# MCU047F_Main.net
KiCad netlist of a schematic drawn in Altium Designer
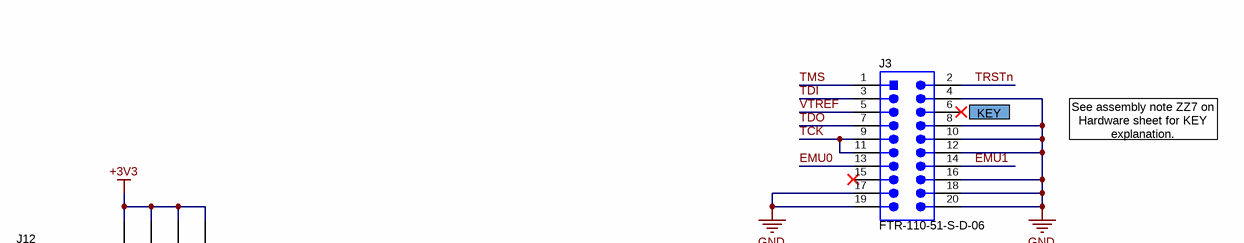
[diagram p0: MCU047F_Main.SchDoc, top left]
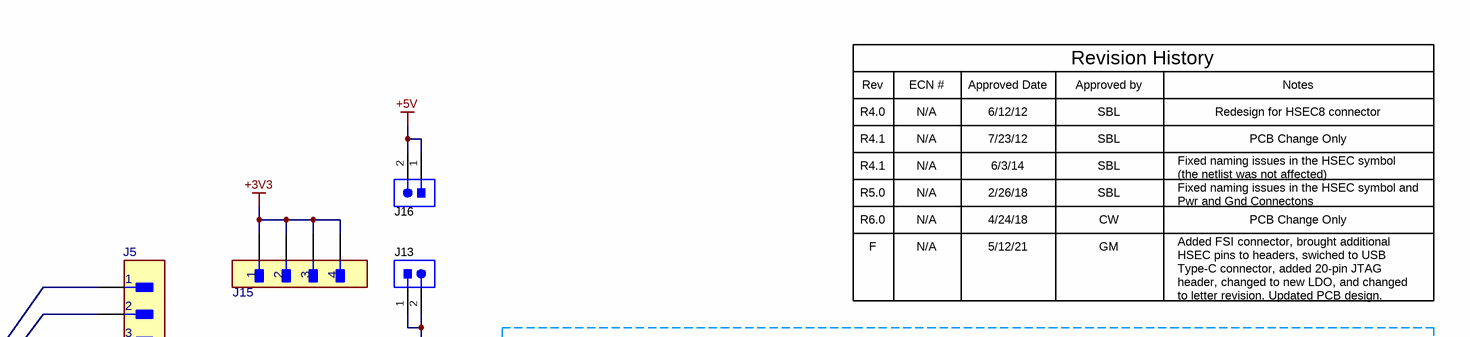
[diagram p1: MCU047F_Main.SchDoc, top right]
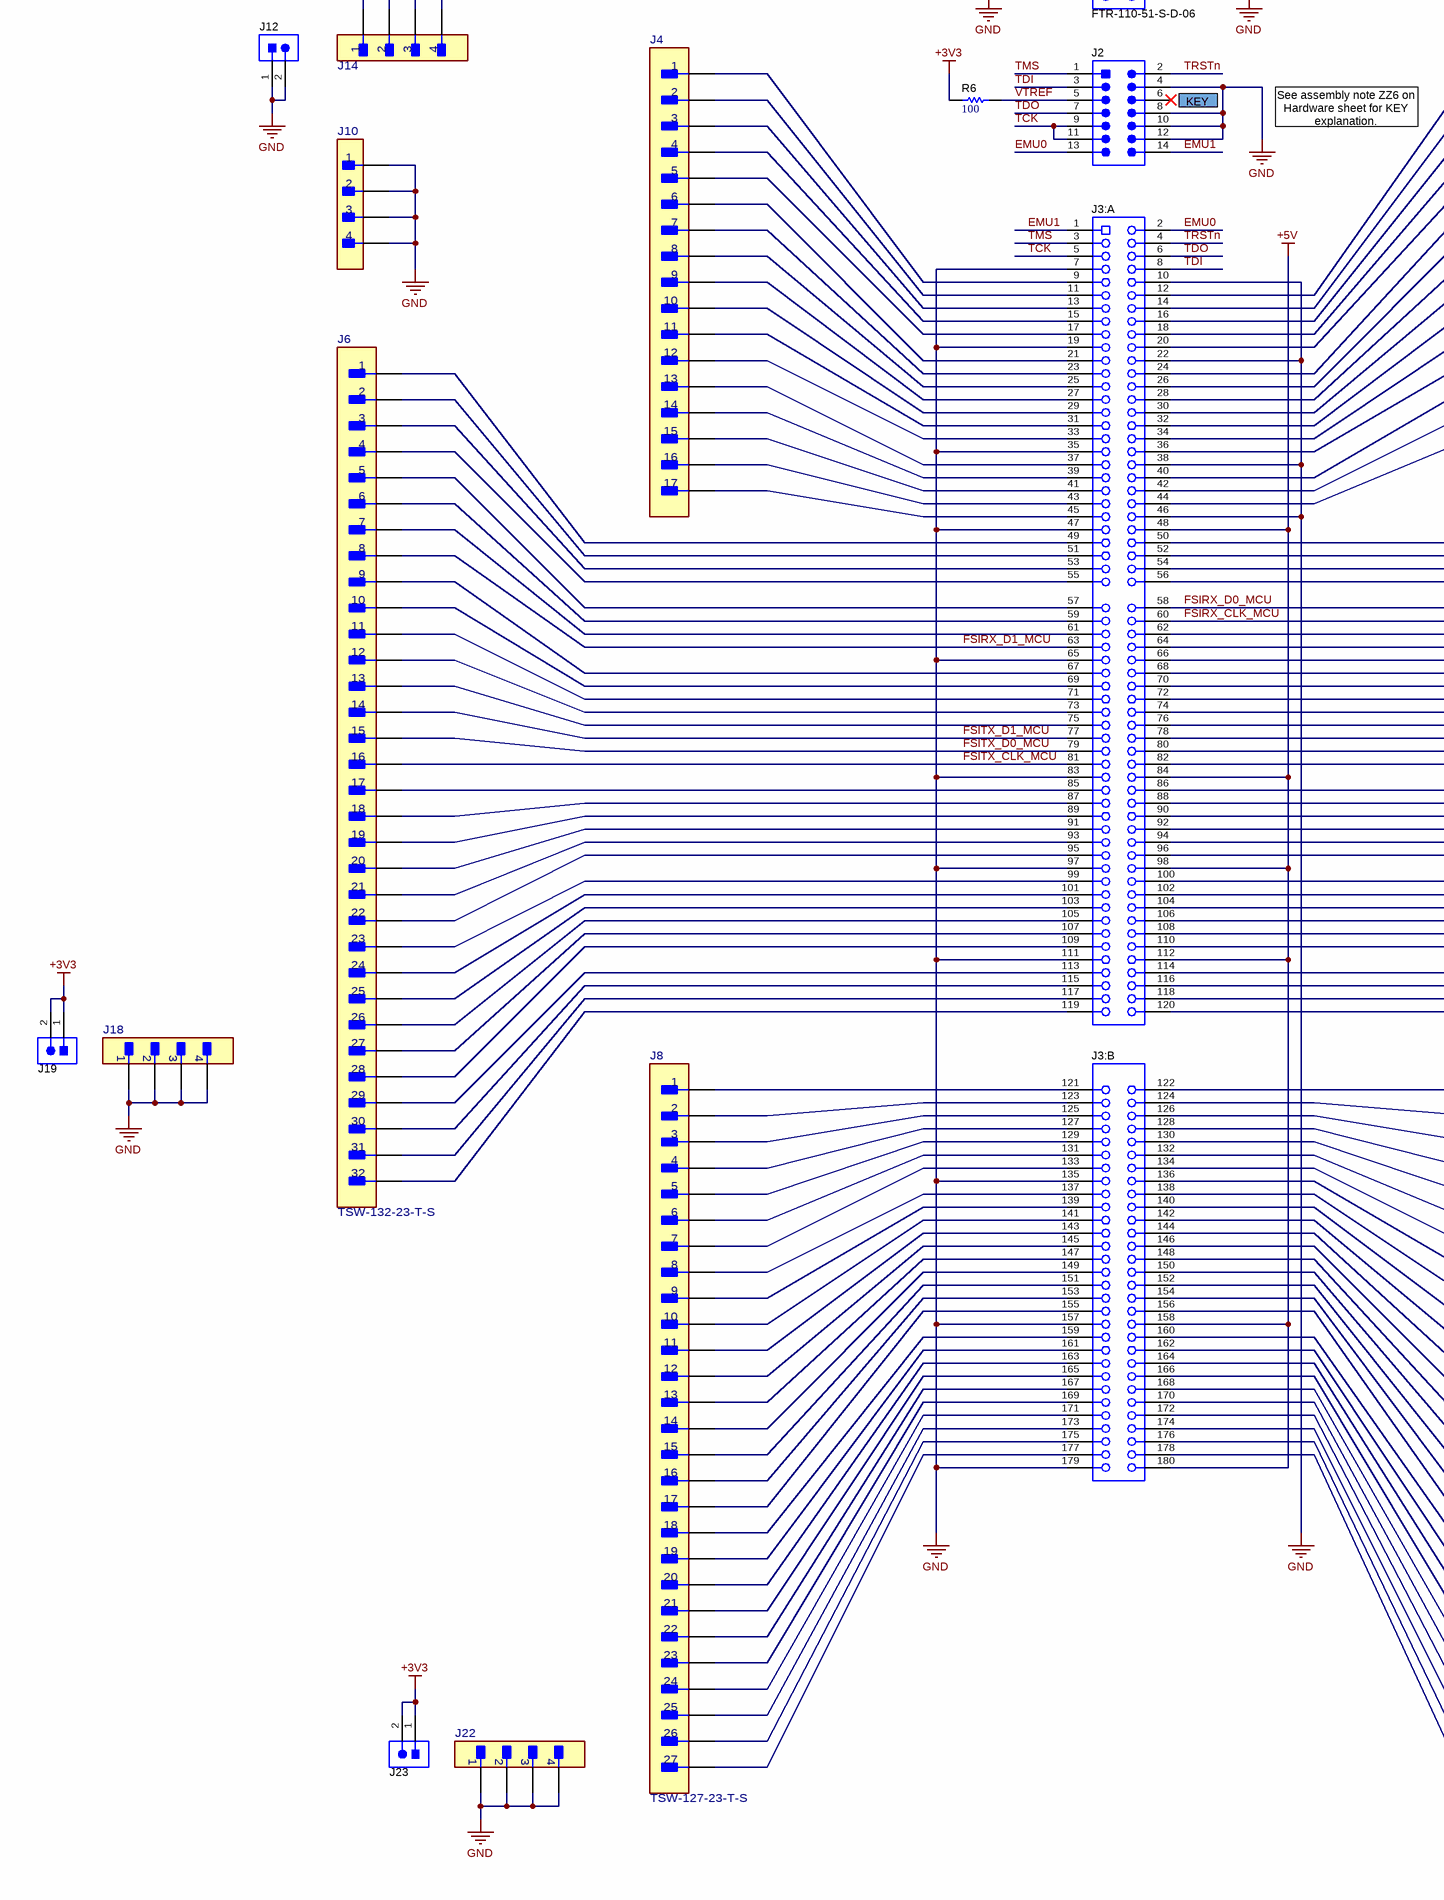
[diagram p2: MCU047F_Main.SchDoc, bottom left]
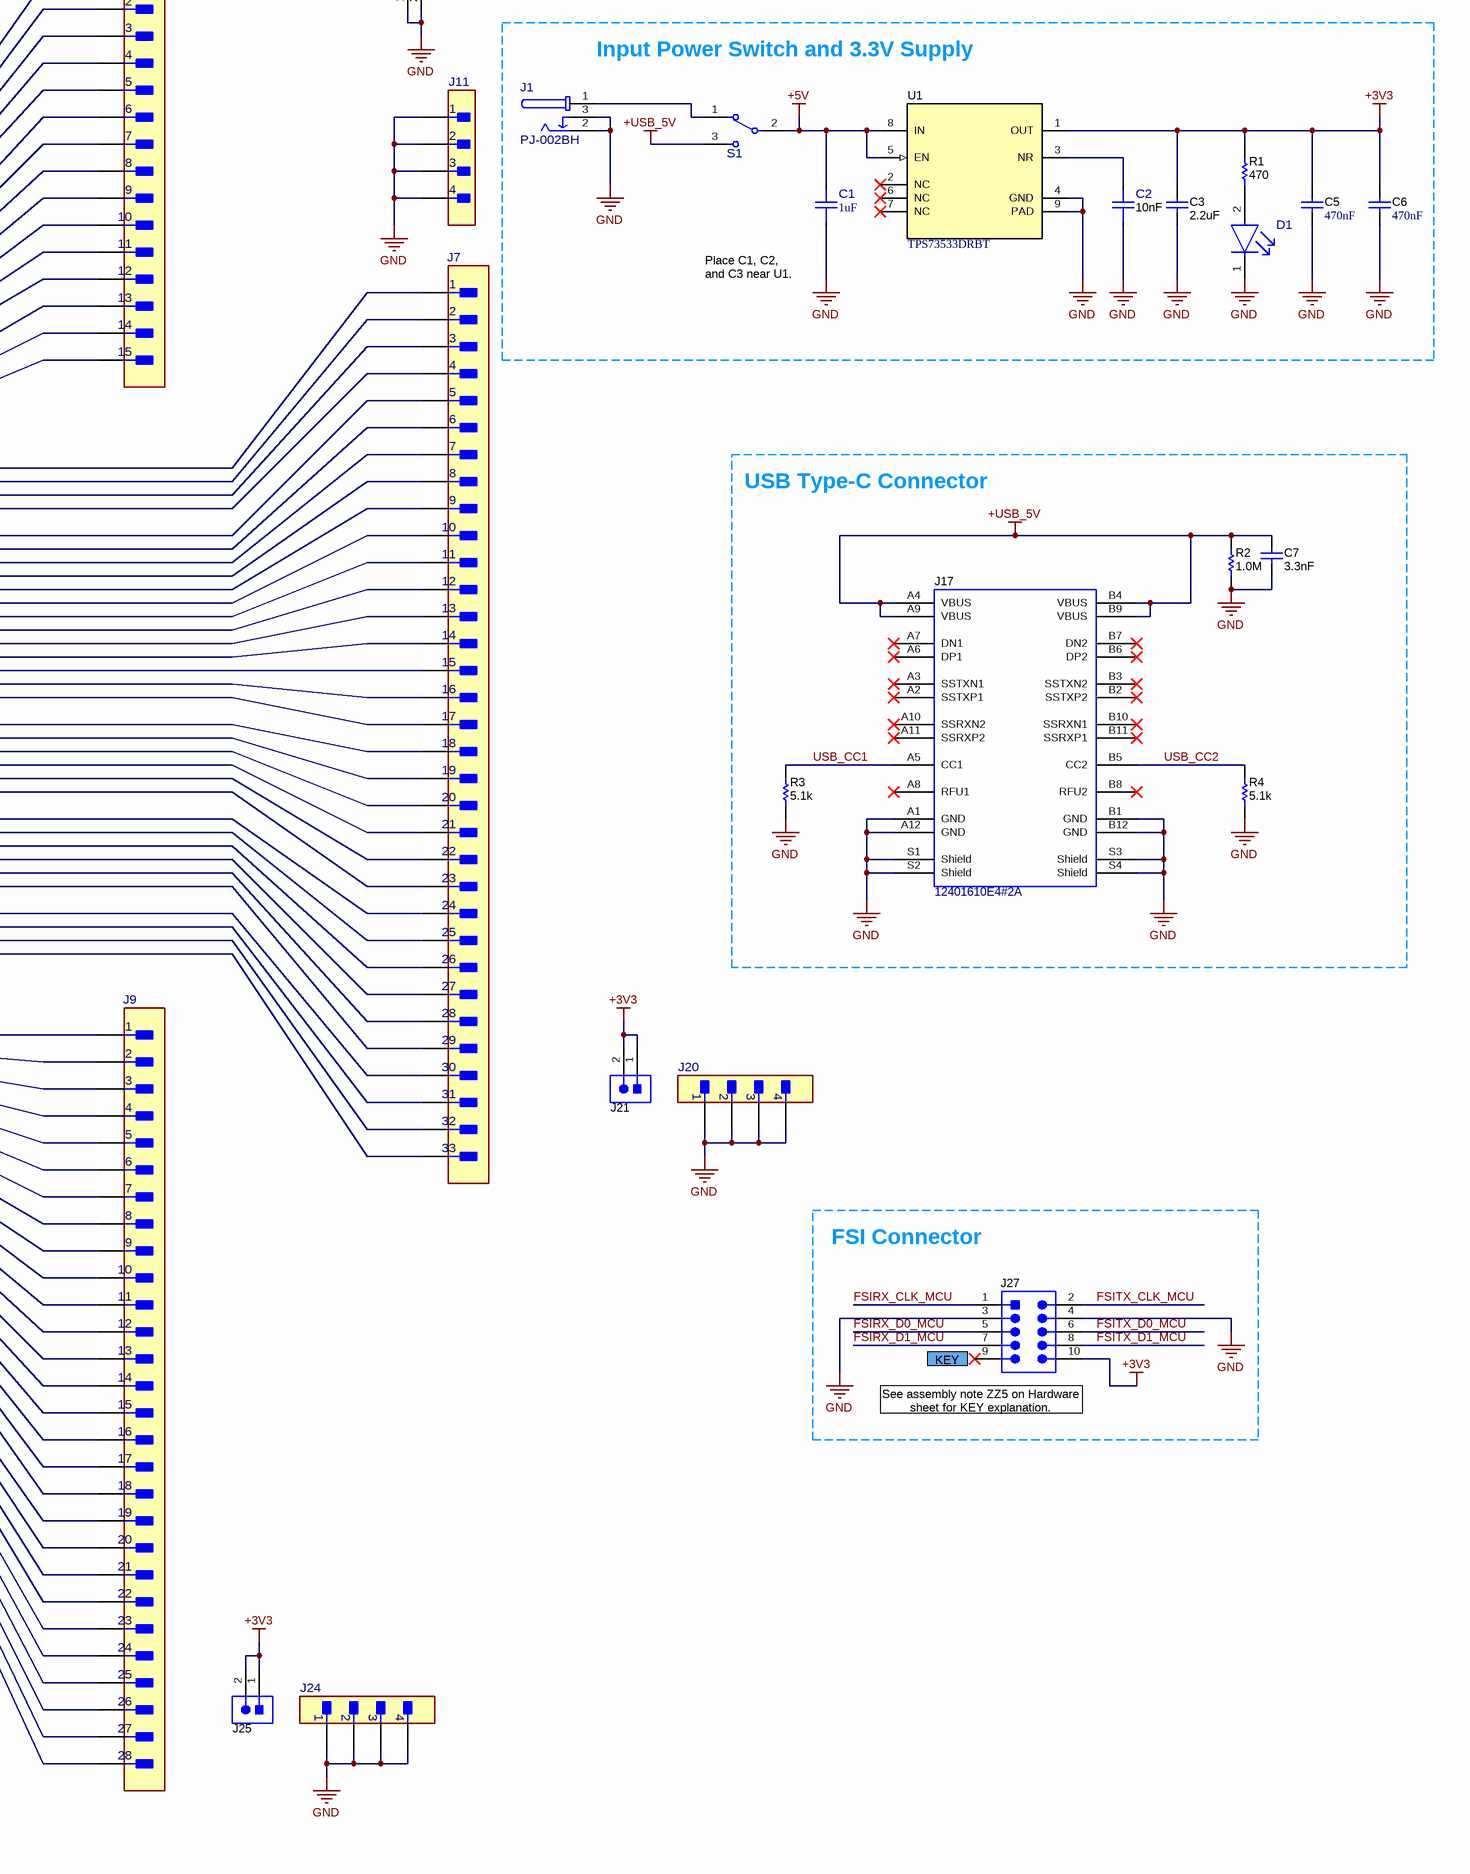
[diagram p3: MCU047F_Main.SchDoc, bottom right]

(export (version "E")
  (design (tool "Eeschema 10.0.6"))
  (components
    (comp (ref "C1")
      (value "C0603C105K8PAC7411")
      (footprint "FP-C0603C105K8PAC7411_0603-MFG")
      (description "1uF ±10% 10V Ceramic Capacitor X5R 0603 (1608 Metric)")
      (fields
        (field (name "MANUFACTURER") "KEMET")
        (field (name "VALUEDISPLAYED") "1uF")
        (field (name "MOUSER PART NUMBER") "80-C0603C105K8PLR")
      )
      (libsource (lib "Altium Vault - TI") (part "SYM-C0603C105K8PAC7411"))
    )
    (comp (ref "C2")
      (value "C0603C103K9RACTU")
      (footprint "FP-C0603C103K9RACTU_0603-MFG")
      (description "10000pF ±10% 6.3V Ceramic Capacitor X7R 0603 (1608 Metric)")
      (fields
        (field (name "DIGIKEY PART NUMBER") "399-8988-1-ND")
        (field (name "MANUFACTURER") "Kemet")
        (field (name "CAP_F") "10nF")
      )
      (libsource (lib "Altium Vault - TI") (part "SYM-C0603C103K9RACTU"))
    )
    (comp (ref "C3")
      (value "JMK107BJ225KAHT")
      (footprint "0603")
      (description "CAP, CERM, 2.2 uF, 6.3 V, +/- 10%, X5R, 0603")
      (fields
        (field (name "MANUFACTURER") "Taiyo Yuden")
        (field (name "VALUEDISPLAYED") "2.2uF")
        (field (name "PUBLISHER") "Texas Instruments")
      )
      (libsource (lib "Altium Vault - TI") (part "Capacitor"))
    )
    (comp (ref "C5")
      (value "0805YC474KAT2A")
      (footprint "0805_HV")
      (description "CAP, CERM, 0.47 uF, 16 V, +/- 10%, X7R, 0805")
      (fields
        (field (name "MANUFACTURER") "AVX")
        (field (name "CAP_F") "470nF")
        (field (name "PUBLISHER") "Texas Instruments")
      )
      (libsource (lib "Altium Vault - TI") (part "Capacitor"))
    )
    (comp (ref "C6")
      (value "0805YC474KAT2A")
      (footprint "0805_HV")
      (description "CAP, CERM, 0.47 uF, 16 V, +/- 10%, X7R, 0805")
      (fields
        (field (name "MANUFACTURER") "AVX")
        (field (name "CAP_F") "470nF")
        (field (name "PUBLISHER") "Texas Instruments")
      )
      (libsource (lib "Altium Vault - TI") (part "Capacitor"))
    )
    (comp (ref "C7")
      (value "C0805C332K5RACTU")
      (footprint "0805_HV")
      (description "CAP, CERM, 3300 pF, 50 V, +/- 10%, X7R, 0805")
      (fields
        (field (name "MANUFACTURER") "Kemet")
        (field (name "CAP_F") "3.3nF")
        (field (name "PUBLISHER") "Texas Instruments")
      )
      (libsource (lib "Altium Vault - TI") (part "Capacitor"))
    )
    (comp (ref "D1")
      (value "PG1112H-TR")
      (footprint "FP-PG1112H-TR_0805-MFG")
      (description "Green 567nm LED Indication - Discrete 2.1V 0805 (2012 Metric)")
      (fields
        (field (name "MOUSER PART NUMBER") "327-PG1112HTR")
        (field (name "MANUFACTURER") "Stanley Electric Co")
      )
      (libsource (lib "Altium Vault - TI") (part "SYM-PG1112H-TR"))
    )
    (comp (ref "J1")
      (value "PJ-002BH")
      (footprint "FP-PJ-002BH_PTH_POWER_CONN_14MM4_9MM0-MFG")
      (fields
        (field (name "MANUFACTURER") "CUI Devices")
        (field (name "DIGIKEY PART NUMBER") "CP-002BH-ND")
        (field (name "MOUSER PART NUMBER") "490-PJ-002BH")
      )
      (libsource (lib "Altium Vault - TI") (part "SYM-PJ-002BH"))
    )
    (comp (ref "J2")
      (value "61301421121")
      (footprint "Wurth_61301421121")
      (description "Header, 2.54mm, 7x2, Gold, TH")
      (fields (field (name "MANUFACTURER") "Wurth Elektronik"))
      (libsource (lib "Altium Vault - TI") (part "Header_7x2"))
    )
    (comp (ref "J3")
      (value "FTR-110-51-S-D-06")
      (footprint "Samtec_FTR-110-51-x-D-06")
      (description "Header, 1.27mm, 10x2, Tin, SMT")
      (fields (field (name "MANUFACTURER") "Samtec"))
      (libsource (lib "Altium Vault - TI") (part "Header_10x2"))
    )
    (comp (ref "J3:A")
      (value "HSEC8-160-01-L-DV-A-BL")
      (footprint "controlCARD-120HSEC")
      (description "C2000 controlCARD-120HSEC connector, SMT")
      (fields (field (name "MANUFACTURER") "Samtec"))
      (libsource (lib "Altium Vault - TI") (part "controlCARD-120HSEC"))
    )
    (comp (ref "J3:B")
      (value "HSEC8-130-01-L-DV-A")
      (footprint "controlCARD-180HSEC-60pinAddon")
      (description "C2000 controlCARD-180HSEC (60-pin addon) connector, SMT")
      (fields (field (name "MANUFACTURER") "Samtec"))
      (libsource (lib "Altium Vault - TI") (part "controlCARD-180HSEC-60pinAddon"))
    )
    (comp (ref "J4")
      (value "TSW-117-23-T-S")
      (footprint "FP-TSW-117-23-T-S_HDR17-MFG")
      (description "Conn Unshrouded Header HDR 17 POS 2.54mm Solder ST Thru-Hole")
      (fields
        (field (name "DIGIKEY PART NUMBER") "SAM1075-17-ND")
        (field (name "MOUSER PART NUMBER") "200-TSW11723TS")
      )
      (libsource (lib "Altium Vault - TI") (part "SYM-TSW-117-23-T-S"))
    )
    (comp (ref "J5")
      (value "TSW-115-23-T-S")
      (footprint "FP-TSW-115-23-T-S_HDR15-MFG")
      (description "Conn Unshrouded Header HDR 15 POS 2.54mm Solder ST Thru-Hole")
      (fields
        (field (name "DIGIKEY PART NUMBER") "SAM1075-15-ND")
        (field (name "MOUSER PART NUMBER") "200-TSW11523TS")
      )
      (libsource (lib "Altium Vault - TI") (part "SYM-TSW-115-23-T-S"))
    )
    (comp (ref "J6")
      (value "TSW-132-23-T-S")
      (footprint "FP-TSW-132-23-T-S_HDR32-MFG")
      (fields
        (field (name "DIGIKEY PART NUMBER") "SAM1075-32-ND")
        (field (name "MOUSER PART NUMBER") "200-TSW13223TS")
        (field (name "MANUFACTURER") "Samtec")
      )
      (libsource (lib "Altium Vault - TI") (part "SYM-TSW-132-23-T-S"))
    )
    (comp (ref "J7")
      (value "TSW-133-23-T-S")
      (footprint "FP-TSW-133-23-T-S_HDR33-MFG")
      (description "Conn Unshrouded Header HDR 33 POS 2.54mm Solder ST Thru-Hole")
      (fields (field (name "OCTOPART PART NUMBER") "26cbefc533f0f90c") (field (name "MANUFACTURER") "Samtec"))
      (libsource (lib "Altium Vault - TI") (part "SYM-TSW-133-23-T-S"))
    )
    (comp (ref "J8")
      (value "TSW-127-23-T-S")
      (footprint "FP-TSW-127-23-T-S_HDR27-MFG")
      (fields (field (name "DIGIKEY PART NUMBER") "SAM1075-27-ND") (field (name "MANUFACTURER") "Samtec"))
      (libsource (lib "Altium Vault - TI") (part "SYM-TSW-127-23-T-S"))
    )
    (comp (ref "J9")
      (value "TSW-128-23-T-S")
      (footprint "FP-TSW-128-23-T-S_HDR28-0")
      (description "Conn Unshrouded Header HDR 28 POS 2.54mm Solder ST Thru-Hole")
      (fields (field (name "DIGIKEY PART NUMBER") "SAM1075-28-ND") (field (name "MANUFACTURER") "Samtec"))
      (libsource (lib "Altium Vault - TI") (part "SYM-TSW-128-23-T-S"))
    )
    (comp (ref "J10")
      (value "TSW-104-23-T-S")
      (footprint "FP-TSW-104-23-T-S_HDR4-MFG")
      (description "Conn Unshrouded Header HDR 4 POS 2.54mm Solder ST Thru-Hole")
      (fields (field (name "MANUFACTURER") "Samtec") (field (name "MOUSER PART NUMBER") "200-TSW10423TS"))
      (libsource (lib "") (part "SYM-TSW-104-23-T-S_1"))
    )
    (comp (ref "J11")
      (value "TSW-104-23-T-S")
      (footprint "FP-TSW-104-23-T-S_HDR4-MFG")
      (description "Conn Unshrouded Header HDR 4 POS 2.54mm Solder ST Thru-Hole")
      (fields (field (name "MANUFACTURER") "Samtec") (field (name "MOUSER PART NUMBER") "200-TSW10423TS"))
      (libsource (lib "") (part "SYM-TSW-104-23-T-S_2"))
    )
    (comp (ref "J12")
      (value "TSW-102-23-T-S")
      (footprint "Samtec_TSW-102-23-X-S")
      (description "Header, 2.54mm, 2x1, Tin, TH")
      (fields (field (name "MANUFACTURER") "Samtec"))
      (libsource (lib "") (part "Header_2x1_1"))
    )
    (comp (ref "J13")
      (value "TSW-102-23-T-S")
      (footprint "Samtec_TSW-102-23-X-S")
      (description "Header, 2.54mm, 2x1, Tin, TH")
      (fields (field (name "MANUFACTURER") "Samtec"))
      (libsource (lib "") (part "Header_2x1_1"))
    )
    (comp (ref "J14")
      (value "TSW-104-23-T-S")
      (footprint "FP-TSW-104-23-T-S_HDR4-MFG")
      (description "Conn Unshrouded Header HDR 4 POS 2.54mm Solder ST Thru-Hole")
      (fields (field (name "MANUFACTURER") "Samtec") (field (name "MOUSER PART NUMBER") "200-TSW10423TS"))
      (libsource (lib "") (part "SYM-TSW-104-23-T-S_3"))
    )
    (comp (ref "J15")
      (value "TSW-104-23-T-S")
      (footprint "FP-TSW-104-23-T-S_HDR4-MFG")
      (description "Conn Unshrouded Header HDR 4 POS 2.54mm Solder ST Thru-Hole")
      (fields (field (name "MANUFACTURER") "Samtec") (field (name "MOUSER PART NUMBER") "200-TSW10423TS"))
      (libsource (lib "") (part "SYM-TSW-104-23-T-S_3"))
    )
    (comp (ref "J16")
      (value "TSW-102-23-T-S")
      (footprint "Samtec_TSW-102-23-X-S")
      (description "Header, 2.54mm, 2x1, Tin, TH")
      (fields (field (name "MANUFACTURER") "Samtec"))
      (libsource (lib "Altium Vault - TI") (part "Header_2x1"))
    )
    (comp (ref "J17")
      (value "12401610E4#2A")
      (footprint "Amphenol_12401610E4_2A")
      (description "Receptacle, 0.5mm, USB TYPE C, R/A, SMT")
      (fields (field (name "MANUFACTURER") "Amphenol Canada") (field (name "PUBLISHER") "Texas Instruments"))
      (libsource (lib "Altium Vault - TI") (part "USB_TYPC-C_4Shield"))
    )
    (comp (ref "J18")
      (value "TSW-104-23-T-S")
      (footprint "FP-TSW-104-23-T-S_HDR4-MFG")
      (description "Conn Unshrouded Header HDR 4 POS 2.54mm Solder ST Thru-Hole")
      (fields (field (name "MANUFACTURER") "Samtec") (field (name "MOUSER PART NUMBER") "200-TSW10423TS"))
      (libsource (lib "Altium Vault - TI") (part "SYM-TSW-104-23-T-S"))
    )
    (comp (ref "J19")
      (value "TSW-102-23-T-S")
      (footprint "Samtec_TSW-102-23-X-S")
      (description "Header, 2.54mm, 2x1, Tin, TH")
      (fields (field (name "MANUFACTURER") "Samtec"))
      (libsource (lib "Altium Vault - TI") (part "Header_2x1"))
    )
    (comp (ref "J20")
      (value "TSW-104-23-T-S")
      (footprint "FP-TSW-104-23-T-S_HDR4-MFG")
      (description "Conn Unshrouded Header HDR 4 POS 2.54mm Solder ST Thru-Hole")
      (fields (field (name "MANUFACTURER") "Samtec") (field (name "MOUSER PART NUMBER") "200-TSW10423TS"))
      (libsource (lib "Altium Vault - TI") (part "SYM-TSW-104-23-T-S"))
    )
    (comp (ref "J21")
      (value "TSW-102-23-T-S")
      (footprint "Samtec_TSW-102-23-X-S")
      (description "Header, 2.54mm, 2x1, Tin, TH")
      (fields (field (name "MANUFACTURER") "Samtec"))
      (libsource (lib "Altium Vault - TI") (part "Header_2x1"))
    )
    (comp (ref "J22")
      (value "TSW-104-23-T-S")
      (footprint "FP-TSW-104-23-T-S_HDR4-MFG")
      (description "Conn Unshrouded Header HDR 4 POS 2.54mm Solder ST Thru-Hole")
      (fields (field (name "MANUFACTURER") "Samtec") (field (name "MOUSER PART NUMBER") "200-TSW10423TS"))
      (libsource (lib "Altium Vault - TI") (part "SYM-TSW-104-23-T-S"))
    )
    (comp (ref "J23")
      (value "TSW-102-23-T-S")
      (footprint "Samtec_TSW-102-23-X-S")
      (description "Header, 2.54mm, 2x1, Tin, TH")
      (fields (field (name "MANUFACTURER") "Samtec"))
      (libsource (lib "Altium Vault - TI") (part "Header_2x1"))
    )
    (comp (ref "J24")
      (value "TSW-104-23-T-S")
      (footprint "FP-TSW-104-23-T-S_HDR4-MFG")
      (description "Conn Unshrouded Header HDR 4 POS 2.54mm Solder ST Thru-Hole")
      (fields (field (name "MANUFACTURER") "Samtec") (field (name "MOUSER PART NUMBER") "200-TSW10423TS"))
      (libsource (lib "Altium Vault - TI") (part "SYM-TSW-104-23-T-S"))
    )
    (comp (ref "J25")
      (value "TSW-102-23-T-S")
      (footprint "Samtec_TSW-102-23-X-S")
      (description "Header, 2.54mm, 2x1, Tin, TH")
      (fields (field (name "MANUFACTURER") "Samtec"))
      (libsource (lib "Altium Vault - TI") (part "Header_2x1"))
    )
    (comp (ref "J27")
      (value "TSW-105-07-G-D")
      (footprint "TSW-105-07-G-D")
      (description "Header, 100mil, 5x2, Gold, TH")
      (fields (field (name "MANUFACTURER") "Samtec"))
      (libsource (lib "Altium Vault - TI") (part "Header_5x2"))
    )
    (comp (ref "R1")
      (value "ERJ-6GEYJ471V")
      (footprint "0805_HV")
      (description "RES, 470, 5%, 0.125 W, AEC-Q200 Grade 0, 0805")
      (fields (field (name "MANUFACTURER") "Panasonic") (field (name "VALUEDISPLAYED") "470"))
      (libsource (lib "Altium Vault - TI") (part "Resistor"))
    )
    (comp (ref "R2")
      (value "ERJ-6GEYJ105V")
      (footprint "0805_HV")
      (description "RES, 1.0 M, 5%, 0.125 W, AEC-Q200 Grade 0, 0805")
      (fields (field (name "MANUFACTURER") "Panasonic") (field (name "VALUEDISPLAYED") "1.0M"))
      (libsource (lib "Altium Vault - TI") (part "Resistor"))
    )
    (comp (ref "R3")
      (value "ERJ-6GEYJ512V")
      (footprint "0805_HV")
      (description "RES, 5.1 k, 5%, 0.125 W, AEC-Q200 Grade 0, 0805")
      (fields (field (name "MANUFACTURER") "Panasonic") (field (name "VALUEDISPLAYED") "5.1k"))
      (libsource (lib "Altium Vault - TI") (part "Resistor"))
    )
    (comp (ref "R4")
      (value "ERJ-6GEYJ512V")
      (footprint "0805_HV")
      (description "RES, 5.1 k, 5%, 0.125 W, AEC-Q200 Grade 0, 0805")
      (fields (field (name "MANUFACTURER") "Panasonic") (field (name "VALUEDISPLAYED") "5.1k"))
      (libsource (lib "Altium Vault - TI") (part "Resistor"))
    )
    (comp (ref "R6")
      (value "ERJ-6GEYJ101V")
      (footprint "0805_HV")
      (description "RES, 100, 5%, 0.125 W, AEC-Q200 Grade 0, 0805")
      (fields (field (name "MANUFACTURER") "Panasonic") (field (name "VALUEDISPLAYED") "100"))
      (libsource (lib "Altium Vault - TI") (part "Resistor"))
    )
    (comp (ref "S1")
      (value "200AWMSP1T1A1M2QE")
      (footprint "FP-200AWMSP1T1A1M2QE_PTH_SW_8MM13_5MM08-MFG")
      (description "Toggle Switch SPDT Through Hole  3A 120V")
      (fields
        (field (name "MANUFACTURER") "E-Switch")
        (field (name "MOUSER PART NUMBER") "612-200AWMSP1T1A1M2Q")
      )
      (libsource (lib "Altium Vault - TI") (part "SYM-200AWMSP1T1A1M2QE"))
    )
    (comp (ref "U1")
      (value "TPS73533DRBT")
      (footprint "DRB0008A")
      (fields (field (name "MANUFACTURER") "Texas Instruments") (field (name "PARTNUMBER") "TPS73533DRBT"))
      (libsource (lib "Altium Vault - TI") (part "TPS735xxDRB"))
    )
  )
  (nets
    (net (code "1") (name "+3V3") (class "Default")
      (node (ref "C3") (pin "2") (pinfunction "2_2") (pintype "passive"))
      (node (ref "C5") (pin "1") (pinfunction "1_1") (pintype "passive"))
      (node (ref "C6") (pin "1") (pinfunction "1_1") (pintype "passive"))
      (node (ref "J14") (pin "1") (pinfunction "1_1") (pintype "passive"))
      (node (ref "J14") (pin "2") (pinfunction "2_2") (pintype "passive"))
      (node (ref "J14") (pin "3") (pinfunction "3_3") (pintype "passive"))
      (node (ref "J14") (pin "4") (pinfunction "4_4") (pintype "passive"))
      (node (ref "J15") (pin "1") (pinfunction "1_1") (pintype "passive"))
      (node (ref "J15") (pin "2") (pinfunction "2_2") (pintype "passive"))
      (node (ref "J15") (pin "3") (pinfunction "3_3") (pintype "passive"))
      (node (ref "J15") (pin "4") (pinfunction "4_4") (pintype "passive"))
      (node (ref "J19") (pin "1") (pinfunction "1_1") (pintype "passive"))
      (node (ref "J19") (pin "2") (pinfunction "2_2") (pintype "passive"))
      (node (ref "J21") (pin "1") (pinfunction "1_1") (pintype "passive"))
      (node (ref "J21") (pin "2") (pinfunction "2_2") (pintype "passive"))
      (node (ref "J23") (pin "1") (pinfunction "1_1") (pintype "passive"))
      (node (ref "J23") (pin "2") (pinfunction "2_2") (pintype "passive"))
      (node (ref "J25") (pin "1") (pinfunction "1_1") (pintype "passive"))
      (node (ref "J25") (pin "2") (pinfunction "2_2") (pintype "passive"))
      (node (ref "J27") (pin "10") (pinfunction "10_10") (pintype "passive"))
      (node (ref "R1") (pin "2") (pinfunction "2_2") (pintype "passive"))
      (node (ref "R6") (pin "1") (pinfunction "1_1") (pintype "passive"))
      (node (ref "U1") (pin "1") (pinfunction "OUT_1") (pintype "power_in"))
    )
    (net (code "2") (name "+5V") (class "Default")
      (node (ref "C1") (pin "2") (pinfunction "2_2") (pintype "passive"))
      (node (ref "J16") (pin "1") (pinfunction "1_1") (pintype "passive"))
      (node (ref "J16") (pin "2") (pinfunction "2_2") (pintype "passive"))
      (node (ref "J3:A") (pin "112") (pinfunction "112_112") (pintype "passive"))
      (node (ref "J3:A") (pin "48") (pinfunction "48_48") (pintype "passive"))
      (node (ref "J3:A") (pin "84") (pinfunction "84_84") (pintype "passive"))
      (node (ref "J3:A") (pin "98") (pinfunction "98_98") (pintype "passive"))
      (node (ref "J3:B") (pin "158") (pinfunction "158_158") (pintype "passive"))
      (node (ref "J3:B") (pin "180") (pinfunction "180_180") (pintype "passive"))
      (node (ref "S1") (pin "2") (pinfunction "COM_2") (pintype "passive"))
      (node (ref "U1") (pin "5") (pinfunction "EN_5") (pintype "input"))
      (node (ref "U1") (pin "8") (pinfunction "IN_8") (pintype "power_in"))
    )
    (net (code "3") (name "+USB_5V") (class "Default")
      (node (ref "C7") (pin "1") (pinfunction "1_1") (pintype "passive"))
      (node (ref "J17") (pin "A4") (pinfunction "VBUS_A4") (pintype "passive"))
      (node (ref "J17") (pin "A9") (pinfunction "VBUS_A9") (pintype "passive"))
      (node (ref "J17") (pin "B4") (pinfunction "VBUS_B4") (pintype "passive"))
      (node (ref "J17") (pin "B9") (pinfunction "VBUS_B9") (pintype "passive"))
      (node (ref "R2") (pin "2") (pinfunction "2_2") (pintype "passive"))
      (node (ref "S1") (pin "3") (pinfunction "3_3") (pintype "passive"))
    )
    (net (code "4") (name "/EMU0") (class "Default")
      (node (ref "J2") (pin "13") (pinfunction "13_13") (pintype "passive"))
      (node (ref "J3") (pin "13") (pinfunction "13_13") (pintype "passive"))
      (node (ref "J3:A") (pin "2") (pinfunction "2_2") (pintype "passive"))
    )
    (net (code "5") (name "/EMU1") (class "Default")
      (node (ref "J2") (pin "14") (pinfunction "14_14") (pintype "passive"))
      (node (ref "J3") (pin "14") (pinfunction "14_14") (pintype "passive"))
      (node (ref "J3:A") (pin "1") (pinfunction "1_1") (pintype "passive"))
    )
    (net (code "6") (name "/FSIRX_CLK_MCU") (class "Default")
      (node (ref "J27") (pin "1") (pinfunction "1_1") (pintype "passive"))
      (node (ref "J3:A") (pin "60") (pinfunction "60_60") (pintype "passive"))
      (node (ref "J7") (pin "6") (pinfunction "6_6") (pintype "passive"))
    )
    (net (code "7") (name "/FSIRX_D0_MCU") (class "Default")
      (node (ref "J27") (pin "5") (pinfunction "5_5") (pintype "passive"))
      (node (ref "J3:A") (pin "58") (pinfunction "58_58") (pintype "passive"))
      (node (ref "J7") (pin "5") (pinfunction "5_5") (pintype "passive"))
    )
    (net (code "8") (name "/FSIRX_D1_MCU") (class "Default")
      (node (ref "J27") (pin "7") (pinfunction "7_7") (pintype "passive"))
      (node (ref "J3:A") (pin "63") (pinfunction "63_63") (pintype "passive"))
      (node (ref "J6") (pin "8") (pinfunction "8_8") (pintype "passive"))
    )
    (net (code "9") (name "/FSITX_CLK_MCU") (class "Default")
      (node (ref "J27") (pin "2") (pinfunction "2_2") (pintype "passive"))
      (node (ref "J3:A") (pin "81") (pinfunction "81_81") (pintype "passive"))
      (node (ref "J6") (pin "16") (pinfunction "16_16") (pintype "passive"))
    )
    (net (code "10") (name "/FSITX_D0_MCU") (class "Default")
      (node (ref "J27") (pin "6") (pinfunction "6_6") (pintype "passive"))
      (node (ref "J3:A") (pin "79") (pinfunction "79_79") (pintype "passive"))
      (node (ref "J6") (pin "15") (pinfunction "15_15") (pintype "passive"))
    )
    (net (code "11") (name "/FSITX_D1_MCU") (class "Default")
      (node (ref "J27") (pin "8") (pinfunction "8_8") (pintype "passive"))
      (node (ref "J3:A") (pin "77") (pinfunction "77_77") (pintype "passive"))
      (node (ref "J6") (pin "14") (pinfunction "14_14") (pintype "passive"))
    )
    (net (code "12") (name "/TCK") (class "Default")
      (node (ref "J2") (pin "11") (pinfunction "11_11") (pintype "passive"))
      (node (ref "J2") (pin "9") (pinfunction "9_9") (pintype "passive"))
      (node (ref "J3") (pin "11") (pinfunction "11_11") (pintype "passive"))
      (node (ref "J3") (pin "9") (pinfunction "9_9") (pintype "passive"))
      (node (ref "J3:A") (pin "5") (pinfunction "5_5") (pintype "passive"))
    )
    (net (code "13") (name "/TDI") (class "Default")
      (node (ref "J2") (pin "3") (pinfunction "3_3") (pintype "passive"))
      (node (ref "J3") (pin "3") (pinfunction "3_3") (pintype "passive"))
      (node (ref "J3:A") (pin "8") (pinfunction "8_8") (pintype "passive"))
    )
    (net (code "14") (name "/TDO") (class "Default")
      (node (ref "J2") (pin "7") (pinfunction "7_7") (pintype "passive"))
      (node (ref "J3") (pin "7") (pinfunction "7_7") (pintype "passive"))
      (node (ref "J3:A") (pin "6") (pinfunction "6_6") (pintype "passive"))
    )
    (net (code "15") (name "/TMS") (class "Default")
      (node (ref "J2") (pin "1") (pinfunction "1_1") (pintype "passive"))
      (node (ref "J3") (pin "1") (pinfunction "1_1") (pintype "passive"))
      (node (ref "J3:A") (pin "3") (pinfunction "3_3") (pintype "passive"))
    )
    (net (code "16") (name "/TRSTn") (class "Default")
      (node (ref "J2") (pin "2") (pinfunction "2_2") (pintype "passive"))
      (node (ref "J3") (pin "2") (pinfunction "2_2") (pintype "passive"))
      (node (ref "J3:A") (pin "4") (pinfunction "4_4") (pintype "passive"))
    )
    (net (code "17") (name "/USB_CC1") (class "Default")
      (node (ref "J17") (pin "A5") (pinfunction "CC1_A5") (pintype "passive"))
      (node (ref "R3") (pin "2") (pinfunction "2_2") (pintype "passive"))
    )
    (net (code "18") (name "/USB_CC2") (class "Default")
      (node (ref "J17") (pin "B5") (pinfunction "CC2_B5") (pintype "passive"))
      (node (ref "R4") (pin "2") (pinfunction "2_2") (pintype "passive"))
    )
    (net (code "19") (name "/VTREF") (class "Default")
      (node (ref "J2") (pin "5") (pinfunction "5_5") (pintype "passive"))
      (node (ref "J3") (pin "5") (pinfunction "5_5") (pintype "passive"))
      (node (ref "R6") (pin "2") (pinfunction "2_2") (pintype "passive"))
    )
    (net (code "20") (name "GND") (class "Default")
      (node (ref "C1") (pin "1") (pinfunction "1_1") (pintype "passive"))
      (node (ref "C2") (pin "1") (pinfunction "1_1") (pintype "passive"))
      (node (ref "C3") (pin "1") (pinfunction "1_1") (pintype "passive"))
      (node (ref "C5") (pin "2") (pinfunction "2_2") (pintype "passive"))
      (node (ref "C6") (pin "2") (pinfunction "2_2") (pintype "passive"))
      (node (ref "C7") (pin "2") (pinfunction "2_2") (pintype "passive"))
      (node (ref "D1") (pin "1") (pinfunction "CATHODE_1") (pintype "passive"))
      (node (ref "J1") (pin "2") (pinfunction "2_2") (pintype "passive"))
      (node (ref "J1") (pin "3") (pinfunction "3_3") (pintype "passive"))
      (node (ref "J10") (pin "1") (pinfunction "1_1") (pintype "passive"))
      (node (ref "J10") (pin "2") (pinfunction "2_2") (pintype "passive"))
      (node (ref "J10") (pin "3") (pinfunction "3_3") (pintype "passive"))
      (node (ref "J10") (pin "4") (pinfunction "4_4") (pintype "passive"))
      (node (ref "J11") (pin "1") (pinfunction "1_1") (pintype "passive"))
      (node (ref "J11") (pin "2") (pinfunction "2_2") (pintype "passive"))
      (node (ref "J11") (pin "3") (pinfunction "3_3") (pintype "passive"))
      (node (ref "J11") (pin "4") (pinfunction "4_4") (pintype "passive"))
      (node (ref "J12") (pin "1") (pinfunction "1_1") (pintype "passive"))
      (node (ref "J12") (pin "2") (pinfunction "2_2") (pintype "passive"))
      (node (ref "J13") (pin "1") (pinfunction "1_1") (pintype "passive"))
      (node (ref "J13") (pin "2") (pinfunction "2_2") (pintype "passive"))
      (node (ref "J17") (pin "A1") (pinfunction "GND_A1") (pintype "passive"))
      (node (ref "J17") (pin "A12") (pinfunction "GND_A12") (pintype "passive"))
      (node (ref "J17") (pin "B1") (pinfunction "GND_B1") (pintype "passive"))
      (node (ref "J17") (pin "B12") (pinfunction "GND_B12") (pintype "passive"))
      (node (ref "J17") (pin "S1") (pinfunction "Shield_S1") (pintype "passive"))
      (node (ref "J17") (pin "S2") (pinfunction "Shield_S2") (pintype "passive"))
      (node (ref "J17") (pin "S3") (pinfunction "Shield_S3") (pintype "passive"))
      (node (ref "J17") (pin "S4") (pinfunction "Shield_S4") (pintype "passive"))
      (node (ref "J18") (pin "1") (pinfunction "1_1") (pintype "passive"))
      (node (ref "J18") (pin "2") (pinfunction "2_2") (pintype "passive"))
      (node (ref "J18") (pin "3") (pinfunction "3_3") (pintype "passive"))
      (node (ref "J18") (pin "4") (pinfunction "4_4") (pintype "passive"))
      (node (ref "J2") (pin "10") (pinfunction "10_10") (pintype "passive"))
      (node (ref "J2") (pin "12") (pinfunction "12_12") (pintype "passive"))
      (node (ref "J2") (pin "4") (pinfunction "4_4") (pintype "passive"))
      (node (ref "J2") (pin "8") (pinfunction "8_8") (pintype "passive"))
      (node (ref "J20") (pin "1") (pinfunction "1_1") (pintype "passive"))
      (node (ref "J20") (pin "2") (pinfunction "2_2") (pintype "passive"))
      (node (ref "J20") (pin "3") (pinfunction "3_3") (pintype "passive"))
      (node (ref "J20") (pin "4") (pinfunction "4_4") (pintype "passive"))
      (node (ref "J22") (pin "1") (pinfunction "1_1") (pintype "passive"))
      (node (ref "J22") (pin "2") (pinfunction "2_2") (pintype "passive"))
      (node (ref "J22") (pin "3") (pinfunction "3_3") (pintype "passive"))
      (node (ref "J22") (pin "4") (pinfunction "4_4") (pintype "passive"))
      (node (ref "J24") (pin "1") (pinfunction "1_1") (pintype "passive"))
      (node (ref "J24") (pin "2") (pinfunction "2_2") (pintype "passive"))
      (node (ref "J24") (pin "3") (pinfunction "3_3") (pintype "passive"))
      (node (ref "J24") (pin "4") (pinfunction "4_4") (pintype "passive"))
      (node (ref "J27") (pin "3") (pinfunction "3_3") (pintype "passive"))
      (node (ref "J27") (pin "4") (pinfunction "4_4") (pintype "passive"))
      (node (ref "J3") (pin "10") (pinfunction "10_10") (pintype "passive"))
      (node (ref "J3") (pin "12") (pinfunction "12_12") (pintype "passive"))
      (node (ref "J3") (pin "16") (pinfunction "16_16") (pintype "passive"))
      (node (ref "J3") (pin "17") (pinfunction "17_17") (pintype "passive"))
      (node (ref "J3") (pin "18") (pinfunction "18_18") (pintype "passive"))
      (node (ref "J3") (pin "19") (pinfunction "19_19") (pintype "passive"))
      (node (ref "J3") (pin "20") (pinfunction "20_20") (pintype "passive"))
      (node (ref "J3") (pin "4") (pinfunction "4_4") (pintype "passive"))
      (node (ref "J3") (pin "8") (pinfunction "8_8") (pintype "passive"))
      (node (ref "J3:A") (pin "10") (pinfunction "10_10") (pintype "passive"))
      (node (ref "J3:A") (pin "111") (pinfunction "111_111") (pintype "passive"))
      (node (ref "J3:A") (pin "19") (pinfunction "19_19") (pintype "passive"))
      (node (ref "J3:A") (pin "22") (pinfunction "22_22") (pintype "passive"))
      (node (ref "J3:A") (pin "35") (pinfunction "35_35") (pintype "passive"))
      (node (ref "J3:A") (pin "38") (pinfunction "38_38") (pintype "passive"))
      (node (ref "J3:A") (pin "46") (pinfunction "46_46") (pintype "passive"))
      (node (ref "J3:A") (pin "47") (pinfunction "47_47") (pintype "passive"))
      (node (ref "J3:A") (pin "65") (pinfunction "65_65") (pintype "passive"))
      (node (ref "J3:A") (pin "7") (pinfunction "7_7") (pintype "passive"))
      (node (ref "J3:A") (pin "83") (pinfunction "83_83") (pintype "passive"))
      (node (ref "J3:A") (pin "97") (pinfunction "97_97") (pintype "passive"))
      (node (ref "J3:B") (pin "135") (pinfunction "135_135") (pintype "passive"))
      (node (ref "J3:B") (pin "157") (pinfunction "157_157") (pintype "passive"))
      (node (ref "J3:B") (pin "179") (pinfunction "179_179") (pintype "passive"))
      (node (ref "R2") (pin "1") (pinfunction "1_1") (pintype "passive"))
      (node (ref "R3") (pin "1") (pinfunction "1_1") (pintype "passive"))
      (node (ref "R4") (pin "1") (pinfunction "1_1") (pintype "passive"))
      (node (ref "U1") (pin "4") (pinfunction "GND_4") (pintype "power_in"))
      (node (ref "U1") (pin "9") (pinfunction "PAD_9") (pintype "power_in"))
    )
    (net (code "21") (name "Net-(D1-ANODE)") (class "Default")
      (node (ref "D1") (pin "2") (pinfunction "ANODE_2") (pintype "passive"))
      (node (ref "R1") (pin "1") (pinfunction "1_1") (pintype "passive"))
    )
    (net (code "22") (name "Net-(J1-Pad1)") (class "Default")
      (node (ref "J1") (pin "1") (pinfunction "1_1") (pintype "passive"))
      (node (ref "S1") (pin "1") (pinfunction "1_1") (pintype "passive"))
    )
    (net (code "23") (name "Net-(J3:A-Pad9)") (class "Default")
      (node (ref "J3:A") (pin "9") (pinfunction "9_9") (pintype "passive"))
      (node (ref "J4") (pin "1") (pinfunction "1_1") (pintype "passive"))
    )
    (net (code "24") (name "Net-(J3:A-Pad11)") (class "Default")
      (node (ref "J3:A") (pin "11") (pinfunction "11_11") (pintype "passive"))
      (node (ref "J4") (pin "2") (pinfunction "2_2") (pintype "passive"))
    )
    (net (code "25") (name "Net-(J3:A-Pad12)") (class "Default")
      (node (ref "J3:A") (pin "12") (pinfunction "12_12") (pintype "passive"))
      (node (ref "J5") (pin "1") (pinfunction "1_1") (pintype "passive"))
    )
    (net (code "26") (name "Net-(J3:A-Pad13)") (class "Default")
      (node (ref "J3:A") (pin "13") (pinfunction "13_13") (pintype "passive"))
      (node (ref "J4") (pin "3") (pinfunction "3_3") (pintype "passive"))
    )
    (net (code "27") (name "Net-(J3:A-Pad14)") (class "Default")
      (node (ref "J3:A") (pin "14") (pinfunction "14_14") (pintype "passive"))
      (node (ref "J5") (pin "2") (pinfunction "2_2") (pintype "passive"))
    )
    (net (code "28") (name "Net-(J3:A-Pad15)") (class "Default")
      (node (ref "J3:A") (pin "15") (pinfunction "15_15") (pintype "passive"))
      (node (ref "J4") (pin "4") (pinfunction "4_4") (pintype "passive"))
    )
    (net (code "29") (name "Net-(J3:A-Pad16)") (class "Default")
      (node (ref "J3:A") (pin "16") (pinfunction "16_16") (pintype "passive"))
      (node (ref "J5") (pin "3") (pinfunction "3_3") (pintype "passive"))
    )
    (net (code "30") (name "Net-(J3:A-Pad17)") (class "Default")
      (node (ref "J3:A") (pin "17") (pinfunction "17_17") (pintype "passive"))
      (node (ref "J4") (pin "5") (pinfunction "5_5") (pintype "passive"))
    )
    (net (code "31") (name "Net-(J3:A-Pad18)") (class "Default")
      (node (ref "J3:A") (pin "18") (pinfunction "18_18") (pintype "passive"))
      (node (ref "J5") (pin "4") (pinfunction "4_4") (pintype "passive"))
    )
    (net (code "32") (name "Net-(J3:A-Pad20)") (class "Default")
      (node (ref "J3:A") (pin "20") (pinfunction "20_20") (pintype "passive"))
      (node (ref "J5") (pin "5") (pinfunction "5_5") (pintype "passive"))
    )
    (net (code "33") (name "Net-(J3:A-Pad21)") (class "Default")
      (node (ref "J3:A") (pin "21") (pinfunction "21_21") (pintype "passive"))
      (node (ref "J4") (pin "6") (pinfunction "6_6") (pintype "passive"))
    )
    (net (code "34") (name "Net-(J3:A-Pad23)") (class "Default")
      (node (ref "J3:A") (pin "23") (pinfunction "23_23") (pintype "passive"))
      (node (ref "J4") (pin "7") (pinfunction "7_7") (pintype "passive"))
    )
    (net (code "35") (name "Net-(J3:A-Pad24)") (class "Default")
      (node (ref "J3:A") (pin "24") (pinfunction "24_24") (pintype "passive"))
      (node (ref "J5") (pin "6") (pinfunction "6_6") (pintype "passive"))
    )
    (net (code "36") (name "Net-(J3:A-Pad25)") (class "Default")
      (node (ref "J3:A") (pin "25") (pinfunction "25_25") (pintype "passive"))
      (node (ref "J4") (pin "8") (pinfunction "8_8") (pintype "passive"))
    )
    (net (code "37") (name "Net-(J3:A-Pad26)") (class "Default")
      (node (ref "J3:A") (pin "26") (pinfunction "26_26") (pintype "passive"))
      (node (ref "J5") (pin "7") (pinfunction "7_7") (pintype "passive"))
    )
    (net (code "38") (name "Net-(J3:A-Pad27)") (class "Default")
      (node (ref "J3:A") (pin "27") (pinfunction "27_27") (pintype "passive"))
      (node (ref "J4") (pin "9") (pinfunction "9_9") (pintype "passive"))
    )
    (net (code "39") (name "Net-(J3:A-Pad28)") (class "Default")
      (node (ref "J3:A") (pin "28") (pinfunction "28_28") (pintype "passive"))
      (node (ref "J5") (pin "8") (pinfunction "8_8") (pintype "passive"))
    )
    (net (code "40") (name "Net-(J3:A-Pad29)") (class "Default")
      (node (ref "J3:A") (pin "29") (pinfunction "29_29") (pintype "passive"))
      (node (ref "J4") (pin "10") (pinfunction "10_10") (pintype "passive"))
    )
    (net (code "41") (name "Net-(J3:A-Pad30)") (class "Default")
      (node (ref "J3:A") (pin "30") (pinfunction "30_30") (pintype "passive"))
      (node (ref "J5") (pin "9") (pinfunction "9_9") (pintype "passive"))
    )
    (net (code "42") (name "Net-(J3:A-Pad31)") (class "Default")
      (node (ref "J3:A") (pin "31") (pinfunction "31_31") (pintype "passive"))
      (node (ref "J4") (pin "11") (pinfunction "11_11") (pintype "passive"))
    )
    (net (code "43") (name "Net-(J3:A-Pad32)") (class "Default")
      (node (ref "J3:A") (pin "32") (pinfunction "32_32") (pintype "passive"))
      (node (ref "J5") (pin "10") (pinfunction "10_10") (pintype "passive"))
    )
    (net (code "44") (name "Net-(J3:A-Pad33)") (class "Default")
      (node (ref "J3:A") (pin "33") (pinfunction "33_33") (pintype "passive"))
      (node (ref "J4") (pin "12") (pinfunction "12_12") (pintype "passive"))
    )
    (net (code "45") (name "Net-(J3:A-Pad34)") (class "Default")
      (node (ref "J3:A") (pin "34") (pinfunction "34_34") (pintype "passive"))
      (node (ref "J5") (pin "11") (pinfunction "11_11") (pintype "passive"))
    )
    (net (code "46") (name "Net-(J3:A-Pad36)") (class "Default")
      (node (ref "J3:A") (pin "36") (pinfunction "36_36") (pintype "passive"))
      (node (ref "J5") (pin "12") (pinfunction "12_12") (pintype "passive"))
    )
    (net (code "47") (name "Net-(J3:A-Pad37)") (class "Default")
      (node (ref "J3:A") (pin "37") (pinfunction "37_37") (pintype "passive"))
      (node (ref "J4") (pin "13") (pinfunction "13_13") (pintype "passive"))
    )
    (net (code "48") (name "Net-(J3:A-Pad39)") (class "Default")
      (node (ref "J3:A") (pin "39") (pinfunction "39_39") (pintype "passive"))
      (node (ref "J4") (pin "14") (pinfunction "14_14") (pintype "passive"))
    )
    (net (code "49") (name "Net-(J3:A-Pad40)") (class "Default")
      (node (ref "J3:A") (pin "40") (pinfunction "40_40") (pintype "passive"))
      (node (ref "J5") (pin "13") (pinfunction "13_13") (pintype "passive"))
    )
    (net (code "50") (name "Net-(J3:A-Pad41)") (class "Default")
      (node (ref "J3:A") (pin "41") (pinfunction "41_41") (pintype "passive"))
      (node (ref "J4") (pin "15") (pinfunction "15_15") (pintype "passive"))
    )
    (net (code "51") (name "Net-(J3:A-Pad42)") (class "Default")
      (node (ref "J3:A") (pin "42") (pinfunction "42_42") (pintype "passive"))
      (node (ref "J5") (pin "14") (pinfunction "14_14") (pintype "passive"))
    )
    (net (code "52") (name "Net-(J3:A-Pad43)") (class "Default")
      (node (ref "J3:A") (pin "43") (pinfunction "43_43") (pintype "passive"))
      (node (ref "J4") (pin "16") (pinfunction "16_16") (pintype "passive"))
    )
    (net (code "53") (name "Net-(J3:A-Pad44)") (class "Default")
      (node (ref "J3:A") (pin "44") (pinfunction "44_44") (pintype "passive"))
      (node (ref "J5") (pin "15") (pinfunction "15_15") (pintype "passive"))
    )
    (net (code "54") (name "Net-(J3:A-Pad45)") (class "Default")
      (node (ref "J3:A") (pin "45") (pinfunction "45_45") (pintype "passive"))
      (node (ref "J4") (pin "17") (pinfunction "17_17") (pintype "passive"))
    )
    (net (code "55") (name "Net-(J3:A-Pad49)") (class "Default")
      (node (ref "J3:A") (pin "49") (pinfunction "49_49") (pintype "passive"))
      (node (ref "J6") (pin "1") (pinfunction "1_1") (pintype "passive"))
    )
    (net (code "56") (name "Net-(J3:A-Pad50)") (class "Default")
      (node (ref "J3:A") (pin "50") (pinfunction "50_50") (pintype "passive"))
      (node (ref "J7") (pin "1") (pinfunction "1_1") (pintype "passive"))
    )
    (net (code "57") (name "Net-(J3:A-Pad51)") (class "Default")
      (node (ref "J3:A") (pin "51") (pinfunction "51_51") (pintype "passive"))
      (node (ref "J6") (pin "2") (pinfunction "2_2") (pintype "passive"))
    )
    (net (code "58") (name "Net-(J3:A-Pad52)") (class "Default")
      (node (ref "J3:A") (pin "52") (pinfunction "52_52") (pintype "passive"))
      (node (ref "J7") (pin "2") (pinfunction "2_2") (pintype "passive"))
    )
    (net (code "59") (name "Net-(J3:A-Pad53)") (class "Default")
      (node (ref "J3:A") (pin "53") (pinfunction "53_53") (pintype "passive"))
      (node (ref "J6") (pin "3") (pinfunction "3_3") (pintype "passive"))
    )
    (net (code "60") (name "Net-(J3:A-Pad54)") (class "Default")
      (node (ref "J3:A") (pin "54") (pinfunction "54_54") (pintype "passive"))
      (node (ref "J7") (pin "3") (pinfunction "3_3") (pintype "passive"))
    )
    (net (code "61") (name "Net-(J3:A-Pad55)") (class "Default")
      (node (ref "J3:A") (pin "55") (pinfunction "55_55") (pintype "passive"))
      (node (ref "J6") (pin "4") (pinfunction "4_4") (pintype "passive"))
    )
    (net (code "62") (name "Net-(J3:A-Pad56)") (class "Default")
      (node (ref "J3:A") (pin "56") (pinfunction "56_56") (pintype "passive"))
      (node (ref "J7") (pin "4") (pinfunction "4_4") (pintype "passive"))
    )
    (net (code "63") (name "Net-(J3:A-Pad57)") (class "Default")
      (node (ref "J3:A") (pin "57") (pinfunction "57_57") (pintype "passive"))
      (node (ref "J6") (pin "5") (pinfunction "5_5") (pintype "passive"))
    )
    (net (code "64") (name "Net-(J3:A-Pad59)") (class "Default")
      (node (ref "J3:A") (pin "59") (pinfunction "59_59") (pintype "passive"))
      (node (ref "J6") (pin "6") (pinfunction "6_6") (pintype "passive"))
    )
    (net (code "65") (name "Net-(J3:A-Pad61)") (class "Default")
      (node (ref "J3:A") (pin "61") (pinfunction "61_61") (pintype "passive"))
      (node (ref "J6") (pin "7") (pinfunction "7_7") (pintype "passive"))
    )
    (net (code "66") (name "Net-(J3:A-Pad62)") (class "Default")
      (node (ref "J3:A") (pin "62") (pinfunction "62_62") (pintype "passive"))
      (node (ref "J7") (pin "7") (pinfunction "7_7") (pintype "passive"))
    )
    (net (code "67") (name "Net-(J3:A-Pad64)") (class "Default")
      (node (ref "J3:A") (pin "64") (pinfunction "64_64") (pintype "passive"))
      (node (ref "J7") (pin "8") (pinfunction "8_8") (pintype "passive"))
    )
    (net (code "68") (name "Net-(J3:A-Pad66)") (class "Default")
      (node (ref "J3:A") (pin "66") (pinfunction "66_66") (pintype "passive"))
      (node (ref "J7") (pin "9") (pinfunction "9_9") (pintype "passive"))
    )
    (net (code "69") (name "Net-(J3:A-Pad67)") (class "Default")
      (node (ref "J3:A") (pin "67") (pinfunction "67_67") (pintype "passive"))
      (node (ref "J6") (pin "9") (pinfunction "9_9") (pintype "passive"))
    )
    (net (code "70") (name "Net-(J3:A-Pad68)") (class "Default")
      (node (ref "J3:A") (pin "68") (pinfunction "68_68") (pintype "passive"))
      (node (ref "J7") (pin "10") (pinfunction "10_10") (pintype "passive"))
    )
    (net (code "71") (name "Net-(J3:A-Pad69)") (class "Default")
      (node (ref "J3:A") (pin "69") (pinfunction "69_69") (pintype "passive"))
      (node (ref "J6") (pin "10") (pinfunction "10_10") (pintype "passive"))
    )
    (net (code "72") (name "Net-(J3:A-Pad70)") (class "Default")
      (node (ref "J3:A") (pin "70") (pinfunction "70_70") (pintype "passive"))
      (node (ref "J7") (pin "11") (pinfunction "11_11") (pintype "passive"))
    )
    (net (code "73") (name "Net-(J3:A-Pad71)") (class "Default")
      (node (ref "J3:A") (pin "71") (pinfunction "71_71") (pintype "passive"))
      (node (ref "J6") (pin "11") (pinfunction "11_11") (pintype "passive"))
    )
    (net (code "74") (name "Net-(J3:A-Pad72)") (class "Default")
      (node (ref "J3:A") (pin "72") (pinfunction "72_72") (pintype "passive"))
      (node (ref "J7") (pin "12") (pinfunction "12_12") (pintype "passive"))
    )
    (net (code "75") (name "Net-(J3:A-Pad73)") (class "Default")
      (node (ref "J3:A") (pin "73") (pinfunction "73_73") (pintype "passive"))
      (node (ref "J6") (pin "12") (pinfunction "12_12") (pintype "passive"))
    )
    (net (code "76") (name "Net-(J3:A-Pad74)") (class "Default")
      (node (ref "J3:A") (pin "74") (pinfunction "74_74") (pintype "passive"))
      (node (ref "J7") (pin "13") (pinfunction "13_13") (pintype "passive"))
    )
    (net (code "77") (name "Net-(J3:A-Pad75)") (class "Default")
      (node (ref "J3:A") (pin "75") (pinfunction "75_75") (pintype "passive"))
      (node (ref "J6") (pin "13") (pinfunction "13_13") (pintype "passive"))
    )
    (net (code "78") (name "Net-(J3:A-Pad76)") (class "Default")
      (node (ref "J3:A") (pin "76") (pinfunction "76_76") (pintype "passive"))
      (node (ref "J7") (pin "14") (pinfunction "14_14") (pintype "passive"))
    )
    (net (code "79") (name "Net-(J3:A-Pad78)") (class "Default")
      (node (ref "J3:A") (pin "78") (pinfunction "78_78") (pintype "passive"))
      (node (ref "J7") (pin "15") (pinfunction "15_15") (pintype "passive"))
    )
    (net (code "80") (name "Net-(J3:A-Pad80)") (class "Default")
      (node (ref "J3:A") (pin "80") (pinfunction "80_80") (pintype "passive"))
      (node (ref "J7") (pin "16") (pinfunction "16_16") (pintype "passive"))
    )
    (net (code "81") (name "Net-(J3:A-Pad82)") (class "Default")
      (node (ref "J3:A") (pin "82") (pinfunction "82_82") (pintype "passive"))
      (node (ref "J7") (pin "17") (pinfunction "17_17") (pintype "passive"))
    )
    (net (code "82") (name "Net-(J3:A-Pad85)") (class "Default")
      (node (ref "J3:A") (pin "85") (pinfunction "85_85") (pintype "passive"))
      (node (ref "J6") (pin "17") (pinfunction "17_17") (pintype "passive"))
    )
    (net (code "83") (name "Net-(J3:A-Pad86)") (class "Default")
      (node (ref "J3:A") (pin "86") (pinfunction "86_86") (pintype "passive"))
      (node (ref "J7") (pin "18") (pinfunction "18_18") (pintype "passive"))
    )
    (net (code "84") (name "Net-(J3:A-Pad87)") (class "Default")
      (node (ref "J3:A") (pin "87") (pinfunction "87_87") (pintype "passive"))
      (node (ref "J6") (pin "18") (pinfunction "18_18") (pintype "passive"))
    )
    (net (code "85") (name "Net-(J3:A-Pad88)") (class "Default")
      (node (ref "J3:A") (pin "88") (pinfunction "88_88") (pintype "passive"))
      (node (ref "J7") (pin "19") (pinfunction "19_19") (pintype "passive"))
    )
    (net (code "86") (name "Net-(J3:A-Pad89)") (class "Default")
      (node (ref "J3:A") (pin "89") (pinfunction "89_89") (pintype "passive"))
      (node (ref "J6") (pin "19") (pinfunction "19_19") (pintype "passive"))
    )
    (net (code "87") (name "Net-(J3:A-Pad90)") (class "Default")
      (node (ref "J3:A") (pin "90") (pinfunction "90_90") (pintype "passive"))
      (node (ref "J7") (pin "20") (pinfunction "20_20") (pintype "passive"))
    )
    (net (code "88") (name "Net-(J3:A-Pad91)") (class "Default")
      (node (ref "J3:A") (pin "91") (pinfunction "91_91") (pintype "passive"))
      (node (ref "J6") (pin "20") (pinfunction "20_20") (pintype "passive"))
    )
    (net (code "89") (name "Net-(J3:A-Pad92)") (class "Default")
      (node (ref "J3:A") (pin "92") (pinfunction "92_92") (pintype "passive"))
      (node (ref "J7") (pin "21") (pinfunction "21_21") (pintype "passive"))
    )
    (net (code "90") (name "Net-(J3:A-Pad93)") (class "Default")
      (node (ref "J3:A") (pin "93") (pinfunction "93_93") (pintype "passive"))
      (node (ref "J6") (pin "21") (pinfunction "21_21") (pintype "passive"))
    )
    (net (code "91") (name "Net-(J3:A-Pad94)") (class "Default")
      (node (ref "J3:A") (pin "94") (pinfunction "94_94") (pintype "passive"))
      (node (ref "J7") (pin "22") (pinfunction "22_22") (pintype "passive"))
    )
    (net (code "92") (name "Net-(J3:A-Pad95)") (class "Default")
      (node (ref "J3:A") (pin "95") (pinfunction "95_95") (pintype "passive"))
      (node (ref "J6") (pin "22") (pinfunction "22_22") (pintype "passive"))
    )
    (net (code "93") (name "Net-(J3:A-Pad96)") (class "Default")
      (node (ref "J3:A") (pin "96") (pinfunction "96_96") (pintype "passive"))
      (node (ref "J7") (pin "23") (pinfunction "23_23") (pintype "passive"))
    )
    (net (code "94") (name "Net-(J3:A-Pad99)") (class "Default")
      (node (ref "J3:A") (pin "99") (pinfunction "99_99") (pintype "passive"))
      (node (ref "J6") (pin "23") (pinfunction "23_23") (pintype "passive"))
    )
    (net (code "95") (name "Net-(J3:A-Pad100)") (class "Default")
      (node (ref "J3:A") (pin "100") (pinfunction "100_100") (pintype "passive"))
      (node (ref "J7") (pin "24") (pinfunction "24_24") (pintype "passive"))
    )
    (net (code "96") (name "Net-(J3:A-Pad101)") (class "Default")
      (node (ref "J3:A") (pin "101") (pinfunction "101_101") (pintype "passive"))
      (node (ref "J6") (pin "24") (pinfunction "24_24") (pintype "passive"))
    )
    (net (code "97") (name "Net-(J3:A-Pad102)") (class "Default")
      (node (ref "J3:A") (pin "102") (pinfunction "102_102") (pintype "passive"))
      (node (ref "J7") (pin "25") (pinfunction "25_25") (pintype "passive"))
    )
    (net (code "98") (name "Net-(J3:A-Pad103)") (class "Default")
      (node (ref "J3:A") (pin "103") (pinfunction "103_103") (pintype "passive"))
      (node (ref "J6") (pin "25") (pinfunction "25_25") (pintype "passive"))
    )
    (net (code "99") (name "Net-(J3:A-Pad104)") (class "Default")
      (node (ref "J3:A") (pin "104") (pinfunction "104_104") (pintype "passive"))
      (node (ref "J7") (pin "26") (pinfunction "26_26") (pintype "passive"))
    )
    (net (code "100") (name "Net-(J3:A-Pad105)") (class "Default")
      (node (ref "J3:A") (pin "105") (pinfunction "105_105") (pintype "passive"))
      (node (ref "J6") (pin "26") (pinfunction "26_26") (pintype "passive"))
    )
    (net (code "101") (name "Net-(J3:A-Pad106)") (class "Default")
      (node (ref "J3:A") (pin "106") (pinfunction "106_106") (pintype "passive"))
      (node (ref "J7") (pin "27") (pinfunction "27_27") (pintype "passive"))
    )
    (net (code "102") (name "Net-(J3:A-Pad107)") (class "Default")
      (node (ref "J3:A") (pin "107") (pinfunction "107_107") (pintype "passive"))
      (node (ref "J6") (pin "27") (pinfunction "27_27") (pintype "passive"))
    )
    (net (code "103") (name "Net-(J3:A-Pad108)") (class "Default")
      (node (ref "J3:A") (pin "108") (pinfunction "108_108") (pintype "passive"))
      (node (ref "J7") (pin "28") (pinfunction "28_28") (pintype "passive"))
    )
    (net (code "104") (name "Net-(J3:A-Pad109)") (class "Default")
      (node (ref "J3:A") (pin "109") (pinfunction "109_109") (pintype "passive"))
      (node (ref "J6") (pin "28") (pinfunction "28_28") (pintype "passive"))
    )
    (net (code "105") (name "Net-(J3:A-Pad110)") (class "Default")
      (node (ref "J3:A") (pin "110") (pinfunction "110_110") (pintype "passive"))
      (node (ref "J7") (pin "29") (pinfunction "29_29") (pintype "passive"))
    )
    (net (code "106") (name "Net-(J3:A-Pad113)") (class "Default")
      (node (ref "J3:A") (pin "113") (pinfunction "113_113") (pintype "passive"))
      (node (ref "J6") (pin "29") (pinfunction "29_29") (pintype "passive"))
    )
    (net (code "107") (name "Net-(J3:A-Pad114)") (class "Default")
      (node (ref "J3:A") (pin "114") (pinfunction "114_114") (pintype "passive"))
      (node (ref "J7") (pin "30") (pinfunction "30_30") (pintype "passive"))
    )
    (net (code "108") (name "Net-(J3:A-Pad115)") (class "Default")
      (node (ref "J3:A") (pin "115") (pinfunction "115_115") (pintype "passive"))
      (node (ref "J6") (pin "30") (pinfunction "30_30") (pintype "passive"))
    )
    (net (code "109") (name "Net-(J3:A-Pad116)") (class "Default")
      (node (ref "J3:A") (pin "116") (pinfunction "116_116") (pintype "passive"))
      (node (ref "J7") (pin "31") (pinfunction "31_31") (pintype "passive"))
    )
    (net (code "110") (name "Net-(J3:A-Pad117)") (class "Default")
      (node (ref "J3:A") (pin "117") (pinfunction "117_117") (pintype "passive"))
      (node (ref "J6") (pin "31") (pinfunction "31_31") (pintype "passive"))
    )
    (net (code "111") (name "Net-(J3:A-Pad118)") (class "Default")
      (node (ref "J3:A") (pin "118") (pinfunction "118_118") (pintype "passive"))
      (node (ref "J7") (pin "32") (pinfunction "32_32") (pintype "passive"))
    )
    (net (code "112") (name "Net-(J3:A-Pad119)") (class "Default")
      (node (ref "J3:A") (pin "119") (pinfunction "119_119") (pintype "passive"))
      (node (ref "J6") (pin "32") (pinfunction "32_32") (pintype "passive"))
    )
    (net (code "113") (name "Net-(J3:A-Pad120)") (class "Default")
      (node (ref "J3:A") (pin "120") (pinfunction "120_120") (pintype "passive"))
      (node (ref "J7") (pin "33") (pinfunction "33_33") (pintype "passive"))
    )
    (net (code "114") (name "Net-(J3:B-Pad121)") (class "Default")
      (node (ref "J3:B") (pin "121") (pinfunction "121_121") (pintype "passive"))
      (node (ref "J8") (pin "1") (pinfunction "1_1") (pintype "passive"))
    )
    (net (code "115") (name "Net-(J3:B-Pad122)") (class "Default")
      (node (ref "J3:B") (pin "122") (pinfunction "122_122") (pintype "passive"))
      (node (ref "J9") (pin "1") (pinfunction "1_1") (pintype "passive"))
    )
    (net (code "116") (name "Net-(J3:B-Pad123)") (class "Default")
      (node (ref "J3:B") (pin "123") (pinfunction "123_123") (pintype "passive"))
      (node (ref "J8") (pin "2") (pinfunction "2_2") (pintype "passive"))
    )
    (net (code "117") (name "Net-(J3:B-Pad124)") (class "Default")
      (node (ref "J3:B") (pin "124") (pinfunction "124_124") (pintype "passive"))
      (node (ref "J9") (pin "2") (pinfunction "2_2") (pintype "passive"))
    )
    (net (code "118") (name "Net-(J3:B-Pad125)") (class "Default")
      (node (ref "J3:B") (pin "125") (pinfunction "125_125") (pintype "passive"))
      (node (ref "J8") (pin "3") (pinfunction "3_3") (pintype "passive"))
    )
    (net (code "119") (name "Net-(J3:B-Pad126)") (class "Default")
      (node (ref "J3:B") (pin "126") (pinfunction "126_126") (pintype "passive"))
      (node (ref "J9") (pin "3") (pinfunction "3_3") (pintype "passive"))
    )
    (net (code "120") (name "Net-(J3:B-Pad127)") (class "Default")
      (node (ref "J3:B") (pin "127") (pinfunction "127_127") (pintype "passive"))
      (node (ref "J8") (pin "4") (pinfunction "4_4") (pintype "passive"))
    )
    (net (code "121") (name "Net-(J3:B-Pad128)") (class "Default")
      (node (ref "J3:B") (pin "128") (pinfunction "128_128") (pintype "passive"))
      (node (ref "J9") (pin "4") (pinfunction "4_4") (pintype "passive"))
    )
    (net (code "122") (name "Net-(J3:B-Pad129)") (class "Default")
      (node (ref "J3:B") (pin "129") (pinfunction "129_129") (pintype "passive"))
      (node (ref "J8") (pin "5") (pinfunction "5_5") (pintype "passive"))
    )
    (net (code "123") (name "Net-(J3:B-Pad130)") (class "Default")
      (node (ref "J3:B") (pin "130") (pinfunction "130_130") (pintype "passive"))
      (node (ref "J9") (pin "5") (pinfunction "5_5") (pintype "passive"))
    )
    (net (code "124") (name "Net-(J3:B-Pad131)") (class "Default")
      (node (ref "J3:B") (pin "131") (pinfunction "131_131") (pintype "passive"))
      (node (ref "J8") (pin "6") (pinfunction "6_6") (pintype "passive"))
    )
    (net (code "125") (name "Net-(J3:B-Pad132)") (class "Default")
      (node (ref "J3:B") (pin "132") (pinfunction "132_132") (pintype "passive"))
      (node (ref "J9") (pin "6") (pinfunction "6_6") (pintype "passive"))
    )
    (net (code "126") (name "Net-(J3:B-Pad133)") (class "Default")
      (node (ref "J3:B") (pin "133") (pinfunction "133_133") (pintype "passive"))
      (node (ref "J8") (pin "7") (pinfunction "7_7") (pintype "passive"))
    )
    (net (code "127") (name "Net-(J3:B-Pad134)") (class "Default")
      (node (ref "J3:B") (pin "134") (pinfunction "134_134") (pintype "passive"))
      (node (ref "J9") (pin "7") (pinfunction "7_7") (pintype "passive"))
    )
    (net (code "128") (name "Net-(J3:B-Pad136)") (class "Default")
      (node (ref "J3:B") (pin "136") (pinfunction "136_136") (pintype "passive"))
      (node (ref "J9") (pin "8") (pinfunction "8_8") (pintype "passive"))
    )
    (net (code "129") (name "Net-(J3:B-Pad137)") (class "Default")
      (node (ref "J3:B") (pin "137") (pinfunction "137_137") (pintype "passive"))
      (node (ref "J8") (pin "8") (pinfunction "8_8") (pintype "passive"))
    )
    (net (code "130") (name "Net-(J3:B-Pad138)") (class "Default")
      (node (ref "J3:B") (pin "138") (pinfunction "138_138") (pintype "passive"))
      (node (ref "J9") (pin "9") (pinfunction "9_9") (pintype "passive"))
    )
    (net (code "131") (name "Net-(J3:B-Pad139)") (class "Default")
      (node (ref "J3:B") (pin "139") (pinfunction "139_139") (pintype "passive"))
      (node (ref "J8") (pin "9") (pinfunction "9_9") (pintype "passive"))
    )
    (net (code "132") (name "Net-(J3:B-Pad140)") (class "Default")
      (node (ref "J3:B") (pin "140") (pinfunction "140_140") (pintype "passive"))
      (node (ref "J9") (pin "10") (pinfunction "10_10") (pintype "passive"))
    )
    (net (code "133") (name "Net-(J3:B-Pad141)") (class "Default")
      (node (ref "J3:B") (pin "141") (pinfunction "141_141") (pintype "passive"))
      (node (ref "J8") (pin "10") (pinfunction "10_10") (pintype "passive"))
    )
    (net (code "134") (name "Net-(J3:B-Pad142)") (class "Default")
      (node (ref "J3:B") (pin "142") (pinfunction "142_142") (pintype "passive"))
      (node (ref "J9") (pin "11") (pinfunction "11_11") (pintype "passive"))
    )
    (net (code "135") (name "Net-(J3:B-Pad143)") (class "Default")
      (node (ref "J3:B") (pin "143") (pinfunction "143_143") (pintype "passive"))
      (node (ref "J8") (pin "11") (pinfunction "11_11") (pintype "passive"))
    )
    (net (code "136") (name "Net-(J3:B-Pad144)") (class "Default")
      (node (ref "J3:B") (pin "144") (pinfunction "144_144") (pintype "passive"))
      (node (ref "J9") (pin "12") (pinfunction "12_12") (pintype "passive"))
    )
    (net (code "137") (name "Net-(J3:B-Pad145)") (class "Default")
      (node (ref "J3:B") (pin "145") (pinfunction "145_145") (pintype "passive"))
      (node (ref "J8") (pin "12") (pinfunction "12_12") (pintype "passive"))
    )
    (net (code "138") (name "Net-(J3:B-Pad146)") (class "Default")
      (node (ref "J3:B") (pin "146") (pinfunction "146_146") (pintype "passive"))
      (node (ref "J9") (pin "13") (pinfunction "13_13") (pintype "passive"))
    )
    (net (code "139") (name "Net-(J3:B-Pad147)") (class "Default")
      (node (ref "J3:B") (pin "147") (pinfunction "147_147") (pintype "passive"))
      (node (ref "J8") (pin "13") (pinfunction "13_13") (pintype "passive"))
    )
    (net (code "140") (name "Net-(J3:B-Pad148)") (class "Default")
      (node (ref "J3:B") (pin "148") (pinfunction "148_148") (pintype "passive"))
      (node (ref "J9") (pin "14") (pinfunction "14_14") (pintype "passive"))
    )
    (net (code "141") (name "Net-(J3:B-Pad149)") (class "Default")
      (node (ref "J3:B") (pin "149") (pinfunction "149_149") (pintype "passive"))
      (node (ref "J8") (pin "14") (pinfunction "14_14") (pintype "passive"))
    )
    (net (code "142") (name "Net-(J3:B-Pad150)") (class "Default")
      (node (ref "J3:B") (pin "150") (pinfunction "150_150") (pintype "passive"))
      (node (ref "J9") (pin "15") (pinfunction "15_15") (pintype "passive"))
    )
    (net (code "143") (name "Net-(J3:B-Pad151)") (class "Default")
      (node (ref "J3:B") (pin "151") (pinfunction "151_151") (pintype "passive"))
      (node (ref "J8") (pin "15") (pinfunction "15_15") (pintype "passive"))
    )
    (net (code "144") (name "Net-(J3:B-Pad152)") (class "Default")
      (node (ref "J3:B") (pin "152") (pinfunction "152_152") (pintype "passive"))
      (node (ref "J9") (pin "16") (pinfunction "16_16") (pintype "passive"))
    )
    (net (code "145") (name "Net-(J3:B-Pad153)") (class "Default")
      (node (ref "J3:B") (pin "153") (pinfunction "153_153") (pintype "passive"))
      (node (ref "J8") (pin "16") (pinfunction "16_16") (pintype "passive"))
    )
    (net (code "146") (name "Net-(J3:B-Pad154)") (class "Default")
      (node (ref "J3:B") (pin "154") (pinfunction "154_154") (pintype "passive"))
      (node (ref "J9") (pin "17") (pinfunction "17_17") (pintype "passive"))
    )
    (net (code "147") (name "Net-(J3:B-Pad155)") (class "Default")
      (node (ref "J3:B") (pin "155") (pinfunction "155_155") (pintype "passive"))
      (node (ref "J8") (pin "17") (pinfunction "17_17") (pintype "passive"))
    )
    (net (code "148") (name "Net-(J3:B-Pad156)") (class "Default")
      (node (ref "J3:B") (pin "156") (pinfunction "156_156") (pintype "passive"))
      (node (ref "J9") (pin "18") (pinfunction "18_18") (pintype "passive"))
    )
    (net (code "149") (name "Net-(J3:B-Pad159)") (class "Default")
      (node (ref "J3:B") (pin "159") (pinfunction "159_159") (pintype "passive"))
      (node (ref "J8") (pin "18") (pinfunction "18_18") (pintype "passive"))
    )
    (net (code "150") (name "Net-(J3:B-Pad160)") (class "Default")
      (node (ref "J3:B") (pin "160") (pinfunction "160_160") (pintype "passive"))
      (node (ref "J9") (pin "19") (pinfunction "19_19") (pintype "passive"))
    )
    (net (code "151") (name "Net-(J3:B-Pad161)") (class "Default")
      (node (ref "J3:B") (pin "161") (pinfunction "161_161") (pintype "passive"))
      (node (ref "J8") (pin "19") (pinfunction "19_19") (pintype "passive"))
    )
    (net (code "152") (name "Net-(J3:B-Pad162)") (class "Default")
      (node (ref "J3:B") (pin "162") (pinfunction "162_162") (pintype "passive"))
      (node (ref "J9") (pin "20") (pinfunction "20_20") (pintype "passive"))
    )
    (net (code "153") (name "Net-(J3:B-Pad163)") (class "Default")
      (node (ref "J3:B") (pin "163") (pinfunction "163_163") (pintype "passive"))
      (node (ref "J8") (pin "20") (pinfunction "20_20") (pintype "passive"))
    )
    (net (code "154") (name "Net-(J3:B-Pad164)") (class "Default")
      (node (ref "J3:B") (pin "164") (pinfunction "164_164") (pintype "passive"))
      (node (ref "J9") (pin "21") (pinfunction "21_21") (pintype "passive"))
    )
    (net (code "155") (name "Net-(J3:B-Pad165)") (class "Default")
      (node (ref "J3:B") (pin "165") (pinfunction "165_165") (pintype "passive"))
      (node (ref "J8") (pin "21") (pinfunction "21_21") (pintype "passive"))
    )
    (net (code "156") (name "Net-(J3:B-Pad166)") (class "Default")
      (node (ref "J3:B") (pin "166") (pinfunction "166_166") (pintype "passive"))
      (node (ref "J9") (pin "22") (pinfunction "22_22") (pintype "passive"))
    )
    (net (code "157") (name "Net-(J3:B-Pad167)") (class "Default")
      (node (ref "J3:B") (pin "167") (pinfunction "167_167") (pintype "passive"))
      (node (ref "J8") (pin "22") (pinfunction "22_22") (pintype "passive"))
    )
    (net (code "158") (name "Net-(J3:B-Pad168)") (class "Default")
      (node (ref "J3:B") (pin "168") (pinfunction "168_168") (pintype "passive"))
      (node (ref "J9") (pin "23") (pinfunction "23_23") (pintype "passive"))
    )
    (net (code "159") (name "Net-(J3:B-Pad169)") (class "Default")
      (node (ref "J3:B") (pin "169") (pinfunction "169_169") (pintype "passive"))
      (node (ref "J8") (pin "23") (pinfunction "23_23") (pintype "passive"))
    )
    (net (code "160") (name "Net-(J3:B-Pad170)") (class "Default")
      (node (ref "J3:B") (pin "170") (pinfunction "170_170") (pintype "passive"))
      (node (ref "J9") (pin "24") (pinfunction "24_24") (pintype "passive"))
    )
    (net (code "161") (name "Net-(J3:B-Pad171)") (class "Default")
      (node (ref "J3:B") (pin "171") (pinfunction "171_171") (pintype "passive"))
      (node (ref "J8") (pin "24") (pinfunction "24_24") (pintype "passive"))
    )
    (net (code "162") (name "Net-(J3:B-Pad172)") (class "Default")
      (node (ref "J3:B") (pin "172") (pinfunction "172_172") (pintype "passive"))
      (node (ref "J9") (pin "25") (pinfunction "25_25") (pintype "passive"))
    )
    (net (code "163") (name "Net-(J3:B-Pad173)") (class "Default")
      (node (ref "J3:B") (pin "173") (pinfunction "173_173") (pintype "passive"))
      (node (ref "J8") (pin "25") (pinfunction "25_25") (pintype "passive"))
    )
    (net (code "164") (name "Net-(J3:B-Pad174)") (class "Default")
      (node (ref "J3:B") (pin "174") (pinfunction "174_174") (pintype "passive"))
      (node (ref "J9") (pin "26") (pinfunction "26_26") (pintype "passive"))
    )
    (net (code "165") (name "Net-(J3:B-Pad175)") (class "Default")
      (node (ref "J3:B") (pin "175") (pinfunction "175_175") (pintype "passive"))
      (node (ref "J8") (pin "26") (pinfunction "26_26") (pintype "passive"))
    )
    (net (code "166") (name "Net-(J3:B-Pad176)") (class "Default")
      (node (ref "J3:B") (pin "176") (pinfunction "176_176") (pintype "passive"))
      (node (ref "J9") (pin "27") (pinfunction "27_27") (pintype "passive"))
    )
    (net (code "167") (name "Net-(J3:B-Pad177)") (class "Default")
      (node (ref "J3:B") (pin "177") (pinfunction "177_177") (pintype "passive"))
      (node (ref "J8") (pin "27") (pinfunction "27_27") (pintype "passive"))
    )
    (net (code "168") (name "Net-(J3:B-Pad178)") (class "Default")
      (node (ref "J3:B") (pin "178") (pinfunction "178_178") (pintype "passive"))
      (node (ref "J9") (pin "28") (pinfunction "28_28") (pintype "passive"))
    )
    (net (code "169") (name "Net-(U1-NR)") (class "Default")
      (node (ref "C2") (pin "2") (pinfunction "2_2") (pintype "passive"))
      (node (ref "U1") (pin "3") (pinfunction "NR_3") (pintype "passive"))
    )
    (net (code "170") (name "unconnected-(J2-Pad6)") (class "Default")
      (node (ref "J2") (pin "6") (pinfunction "6_6") (pintype "passive+no_connect"))
    )
    (net (code "171") (name "unconnected-(J3-Pad6)") (class "Default")
      (node (ref "J3") (pin "6") (pinfunction "6_6") (pintype "passive+no_connect"))
    )
    (net (code "172") (name "unconnected-(J3-Pad15)") (class "Default")
      (node (ref "J3") (pin "15") (pinfunction "15_15") (pintype "passive+no_connect"))
    )
    (net (code "173") (name "unconnected-(J17-DN1-PadA7)") (class "Default")
      (node (ref "J17") (pin "A7") (pinfunction "DN1_A7") (pintype "passive+no_connect"))
    )
    (net (code "174") (name "unconnected-(J17-DN2-PadB7)") (class "Default")
      (node (ref "J17") (pin "B7") (pinfunction "DN2_B7") (pintype "passive+no_connect"))
    )
    (net (code "175") (name "unconnected-(J17-DP1-PadA6)") (class "Default")
      (node (ref "J17") (pin "A6") (pinfunction "DP1_A6") (pintype "passive+no_connect"))
    )
    (net (code "176") (name "unconnected-(J17-DP2-PadB6)") (class "Default")
      (node (ref "J17") (pin "B6") (pinfunction "DP2_B6") (pintype "passive+no_connect"))
    )
    (net (code "177") (name "unconnected-(J17-RFU1-PadA8)") (class "Default")
      (node (ref "J17") (pin "A8") (pinfunction "RFU1_A8") (pintype "passive+no_connect"))
    )
    (net (code "178") (name "unconnected-(J17-RFU2-PadB8)") (class "Default")
      (node (ref "J17") (pin "B8") (pinfunction "RFU2_B8") (pintype "passive+no_connect"))
    )
    (net (code "179") (name "unconnected-(J17-SSRXN1-PadB10)") (class "Default")
      (node (ref "J17") (pin "B10") (pinfunction "SSRXN1_B10") (pintype "passive+no_connect"))
    )
    (net (code "180") (name "unconnected-(J17-SSRXN2-PadA10)") (class "Default")
      (node (ref "J17") (pin "A10") (pinfunction "SSRXN2_A10") (pintype "passive+no_connect"))
    )
    (net (code "181") (name "unconnected-(J17-SSRXP1-PadB11)") (class "Default")
      (node (ref "J17") (pin "B11") (pinfunction "SSRXP1_B11") (pintype "passive+no_connect"))
    )
    (net (code "182") (name "unconnected-(J17-SSRXP2-PadA11)") (class "Default")
      (node (ref "J17") (pin "A11") (pinfunction "SSRXP2_A11") (pintype "passive+no_connect"))
    )
    (net (code "183") (name "unconnected-(J17-SSTXN1-PadA3)") (class "Default")
      (node (ref "J17") (pin "A3") (pinfunction "SSTXN1_A3") (pintype "passive+no_connect"))
    )
    (net (code "184") (name "unconnected-(J17-SSTXN2-PadB3)") (class "Default")
      (node (ref "J17") (pin "B3") (pinfunction "SSTXN2_B3") (pintype "passive+no_connect"))
    )
    (net (code "185") (name "unconnected-(J17-SSTXP1-PadA2)") (class "Default")
      (node (ref "J17") (pin "A2") (pinfunction "SSTXP1_A2") (pintype "passive+no_connect"))
    )
    (net (code "186") (name "unconnected-(J17-SSTXP2-PadB2)") (class "Default")
      (node (ref "J17") (pin "B2") (pinfunction "SSTXP2_B2") (pintype "passive+no_connect"))
    )
    (net (code "187") (name "unconnected-(J27-Pad9)") (class "Default")
      (node (ref "J27") (pin "9") (pinfunction "9_9") (pintype "passive+no_connect"))
    )
    (net (code "188") (name "unconnected-(U1-NC-Pad2)") (class "Default")
      (node (ref "U1") (pin "2") (pinfunction "NC_2") (pintype "passive+no_connect"))
    )
    (net (code "189") (name "unconnected-(U1-NC-Pad6)") (class "Default")
      (node (ref "U1") (pin "6") (pinfunction "NC_6") (pintype "passive+no_connect"))
    )
    (net (code "190") (name "unconnected-(U1-NC-Pad7)") (class "Default")
      (node (ref "U1") (pin "7") (pinfunction "NC_7") (pintype "passive+no_connect"))
    )
  )
)
